# VNP.net
KiCad netlist of a schematic drawn in EAGLE
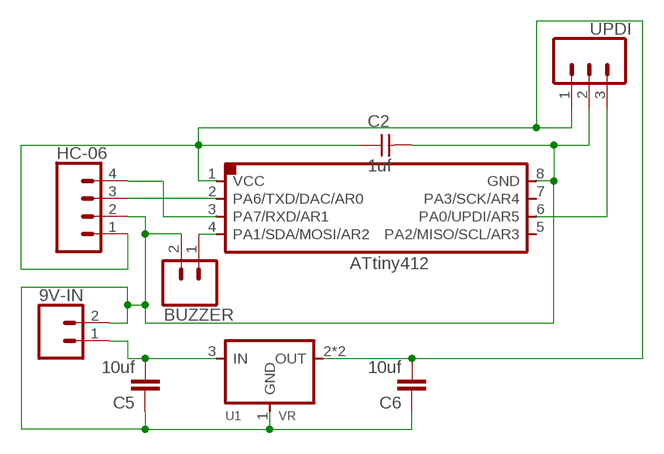
[diagram p0: schematic, sheet 1]

(export (version "E")
  (design (tool "Eeschema 10.0.6"))
  (components
    (comp (ref "9V-IN")
      (value "CONN_02PTH3")
      (footprint "eagle-import:1X02_LONGPADS")
      (libsource (lib "eagle-import") (part "CONN_02PTH3"))
    )
    (comp (ref "BUZZER")
      (value "CONN_02LOCK_LONGPADS")
      (footprint "eagle-import:1X02_LOCK_LONGPADS")
      (libsource (lib "eagle-import") (part "CONN_02LOCK_LONGPADS"))
    )
    (comp (ref "C2")
      (value "1uf")
      (footprint "eagle-import:C1206")
      (libsource (lib "eagle-import") (part "CAP_UNPOLARIZED"))
    )
    (comp (ref "C5")
      (value "10uf")
      (footprint "eagle-import:1206")
      (libsource (lib "eagle-import") (part "CAP1206"))
    )
    (comp (ref "C6")
      (value "10uf")
      (footprint "eagle-import:1206")
      (libsource (lib "eagle-import") (part "CAP1206"))
    )
    (comp (ref "HC-06")
      (value "CONN_04POLAR")
      (footprint "eagle-import:MOLEX-1X4")
      (libsource (lib "eagle-import") (part "CONN_04POLAR"))
    )
    (comp (ref "U$1")
      (value "UC_ATTINY412SI")
      (footprint "eagle-import:SOIC8")
      (libsource (lib "eagle-import") (part "UC_ATTINY412SI"))
    )
    (comp (ref "U1")
      (value "VR")
      (footprint "eagle-import:SOT223")
      (libsource (lib "eagle-import") (part "VR_REGULATOR_SOT223"))
    )
    (comp (ref "UPDI")
      (value "CONN_03SMD_RA_MALE")
      (footprint "eagle-import:1X03_SMD_RA_MALE")
      (libsource (lib "eagle-import") (part "CONN_03SMD_RA_MALE"))
    )
  )
  (nets
    (net (code "1") (name "Net-(U$1-GND)") (class "Default")
      (node (ref "9V-IN") (pin "2") (pinfunction "2_2") (pintype "passive"))
      (node (ref "BUZZER") (pin "2") (pinfunction "2_2") (pintype "passive"))
      (node (ref "C2") (pin "2") (pinfunction "2_2") (pintype "passive"))
      (node (ref "C5") (pin "1") (pinfunction "1_1") (pintype "passive"))
      (node (ref "C6") (pin "1") (pinfunction "1_1") (pintype "passive"))
      (node (ref "HC-06") (pin "2") (pinfunction "2_2") (pintype "passive"))
      (node (ref "U$1") (pin "8") (pinfunction "GND_8") (pintype "bidirectional"))
      (node (ref "U1") (pin "1") (pinfunction "GND_1") (pintype "bidirectional"))
      (node (ref "UPDI") (pin "2") (pinfunction "2_2") (pintype "passive"))
    )
    (net (code "2") (name "Net-(U$1-PA0{slash}UPDI{slash}AR5)") (class "Default")
      (node (ref "U$1") (pin "6") (pinfunction "PA0/UPDI/AR5_6") (pintype "bidirectional"))
      (node (ref "UPDI") (pin "3") (pinfunction "3_3") (pintype "passive"))
    )
    (net (code "3") (name "Net-(U$1-PA1{slash}SDA{slash}MOSI{slash}AR2)") (class "Default")
      (node (ref "BUZZER") (pin "1") (pinfunction "1_1") (pintype "passive"))
      (node (ref "U$1") (pin "4") (pinfunction "PA1/SDA/MOSI/AR2_4") (pintype "bidirectional"))
    )
    (net (code "4") (name "Net-(U$1-PA6{slash}TXD{slash}DAC{slash}AR0)") (class "Default")
      (node (ref "HC-06") (pin "3") (pinfunction "3_3") (pintype "passive"))
      (node (ref "U$1") (pin "2") (pinfunction "PA6/TXD/DAC/AR0_2") (pintype "bidirectional"))
    )
    (net (code "5") (name "Net-(U$1-PA7{slash}RXD{slash}AR1)") (class "Default")
      (node (ref "HC-06") (pin "4") (pinfunction "4_4") (pintype "passive"))
      (node (ref "U$1") (pin "3") (pinfunction "PA7/RXD/AR1_3") (pintype "bidirectional"))
    )
    (net (code "6") (name "Net-(U$1-VCC)") (class "Default")
      (node (ref "C2") (pin "1") (pinfunction "1_1") (pintype "passive"))
      (node (ref "C6") (pin "2") (pinfunction "2_2") (pintype "passive"))
      (node (ref "HC-06") (pin "1") (pinfunction "1_1") (pintype "passive"))
      (node (ref "U$1") (pin "1") (pinfunction "VCC_1") (pintype "bidirectional"))
      (node (ref "U1") (pin "2") (pinfunction "OUT_2") (pintype "bidirectional"))
      (node (ref "U1") (pin "4") (pinfunction "OUT_4") (pintype "bidirectional"))
      (node (ref "UPDI") (pin "1") (pinfunction "1_1") (pintype "passive"))
    )
    (net (code "7") (name "Net-(U1-IN)") (class "Default")
      (node (ref "9V-IN") (pin "1") (pinfunction "1_1") (pintype "passive"))
      (node (ref "C5") (pin "2") (pinfunction "2_2") (pintype "passive"))
      (node (ref "U1") (pin "3") (pinfunction "IN_3") (pintype "bidirectional"))
    )
    (net (code "8") (name "unconnected-(U$1-PA2{slash}MISO{slash}SCL{slash}AR3-Pad5)") (class "Default")
      (node (ref "U$1") (pin "5") (pinfunction "PA2/MISO/SCL/AR3_5") (pintype "bidirectional"))
    )
    (net (code "9") (name "unconnected-(U$1-PA3{slash}SCK{slash}AR4-Pad7)") (class "Default")
      (node (ref "U$1") (pin "7") (pinfunction "PA3/SCK/AR4_7") (pintype "bidirectional"))
    )
  )
)
